# tree_io_leds.net
KiCad netlist of a schematic drawn in Altium Designer
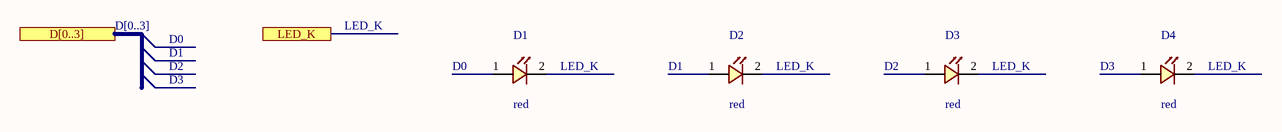
[diagram p0: tree_io.leds.SchDoc]

(export (version "E")
  (design (tool "Eeschema 10.0.6"))
  (components
    (comp (ref "D1") (value "red") (footprint "FenoliteTree:LED0603") (libsource (lib "tree") (part "LED")))
    (comp (ref "D2") (value "red") (footprint "FenoliteTree:LED0603") (libsource (lib "tree") (part "LED")))
    (comp (ref "D3") (value "red") (footprint "FenoliteTree:LED0603") (libsource (lib "tree") (part "LED")))
    (comp (ref "D4") (value "red") (footprint "FenoliteTree:LED0603") (libsource (lib "tree") (part "LED")))
  )
  (nets
    (net (code "1") (name "/D0") (class "Default")
      (node (ref "D1") (pin "1") (pinfunction "A_1") (pintype "passive"))
    )
    (net (code "2") (name "/D1") (class "Default")
      (node (ref "D2") (pin "1") (pinfunction "A_1") (pintype "passive"))
    )
    (net (code "3") (name "/D2") (class "Default")
      (node (ref "D3") (pin "1") (pinfunction "A_1") (pintype "passive"))
    )
    (net (code "4") (name "/D3") (class "Default")
      (node (ref "D4") (pin "1") (pinfunction "A_1") (pintype "passive"))
    )
    (net (code "6") (name "/LED_K") (class "Default")
      (node (ref "D1") (pin "2") (pinfunction "K_2") (pintype "passive"))
      (node (ref "D2") (pin "2") (pinfunction "K_2") (pintype "passive"))
      (node (ref "D3") (pin "2") (pinfunction "K_2") (pintype "passive"))
      (node (ref "D4") (pin "2") (pinfunction "K_2") (pintype "passive"))
    )
  )
)
